# rc28c64rom.net
KiCad netlist of a schematic drawn in EAGLE
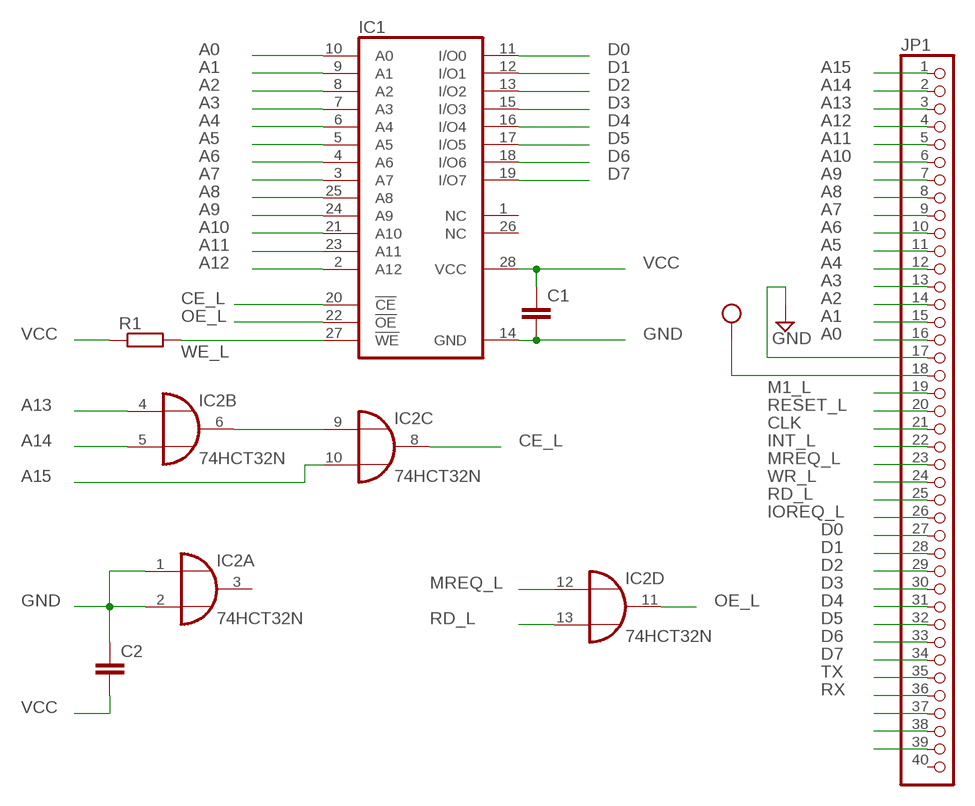
[diagram p0: schematic, sheet 1]

(export (version "E")
  (design (tool "Eeschema 10.0.6"))
  (components
    (comp (ref "C1")
      (value "C-EU025-025X050")
      (footprint "eagle-import:C025-025X050")
      (libsource (lib "eagle-import") (part "C-EU025-025X050"))
    )
    (comp (ref "C2")
      (value "C-EU025-025X050")
      (footprint "eagle-import:C025-025X050")
      (libsource (lib "eagle-import") (part "C-EU025-025X050"))
    )
    (comp (ref "IC1")
      (value "28C64C")
      (footprint "eagle-import:DIL28-6")
      (fields (field (name "MPN") "AT28C64B-15PU"))
      (libsource (lib "eagle-import") (part "28C64C"))
    )
    (comp (ref "IC2")
      (value "74HCT32N")
      (footprint "eagle-import:DIL14")
      (libsource (lib "eagle-import") (part "7432NHCT"))
    )
    (comp (ref "JP1")
      (value "PINHD-1X40")
      (footprint "eagle-import:1X40")
      (libsource (lib "eagle-import") (part "PINHD-1X40"))
    )
    (comp (ref "R1")
      (value "R-EU_0204/7")
      (footprint "eagle-import:0204_7")
      (libsource (lib "eagle-import") (part "R-EU_0204/7"))
    )
  )
  (nets
    (net (code "1") (name "/A0") (class "Default")
      (node (ref "IC1") (pin "10") (pinfunction "A0_10") (pintype "input"))
      (node (ref "JP1") (pin "16") (pinfunction "16_16") (pintype "passive"))
    )
    (net (code "2") (name "/A1") (class "Default")
      (node (ref "IC1") (pin "9") (pinfunction "A1_9") (pintype "input"))
      (node (ref "JP1") (pin "15") (pinfunction "15_15") (pintype "passive"))
    )
    (net (code "3") (name "/A2") (class "Default")
      (node (ref "IC1") (pin "8") (pinfunction "A2_8") (pintype "input"))
      (node (ref "JP1") (pin "14") (pinfunction "14_14") (pintype "passive"))
    )
    (net (code "4") (name "/A3") (class "Default")
      (node (ref "IC1") (pin "7") (pinfunction "A3_7") (pintype "input"))
      (node (ref "JP1") (pin "13") (pinfunction "13_13") (pintype "passive"))
    )
    (net (code "5") (name "/A4") (class "Default")
      (node (ref "IC1") (pin "6") (pinfunction "A4_6") (pintype "input"))
      (node (ref "JP1") (pin "12") (pinfunction "12_12") (pintype "passive"))
    )
    (net (code "6") (name "/A5") (class "Default")
      (node (ref "IC1") (pin "5") (pinfunction "A5_5") (pintype "input"))
      (node (ref "JP1") (pin "11") (pinfunction "11_11") (pintype "passive"))
    )
    (net (code "7") (name "/A6") (class "Default")
      (node (ref "IC1") (pin "4") (pinfunction "A6_4") (pintype "input"))
      (node (ref "JP1") (pin "10") (pinfunction "10_10") (pintype "passive"))
    )
    (net (code "8") (name "/A7") (class "Default")
      (node (ref "IC1") (pin "3") (pinfunction "A7_3") (pintype "input"))
      (node (ref "JP1") (pin "9") (pinfunction "9_9") (pintype "passive"))
    )
    (net (code "9") (name "/A8") (class "Default")
      (node (ref "IC1") (pin "25") (pinfunction "A8_25") (pintype "input"))
      (node (ref "JP1") (pin "8") (pinfunction "8_8") (pintype "passive"))
    )
    (net (code "10") (name "/A9") (class "Default")
      (node (ref "IC1") (pin "24") (pinfunction "A9_24") (pintype "input"))
      (node (ref "JP1") (pin "7") (pinfunction "7_7") (pintype "passive"))
    )
    (net (code "11") (name "/A10") (class "Default")
      (node (ref "IC1") (pin "21") (pinfunction "A10_21") (pintype "input"))
      (node (ref "JP1") (pin "6") (pinfunction "6_6") (pintype "passive"))
    )
    (net (code "12") (name "/A11") (class "Default")
      (node (ref "IC1") (pin "23") (pinfunction "A11_23") (pintype "input"))
      (node (ref "JP1") (pin "5") (pinfunction "5_5") (pintype "passive"))
    )
    (net (code "13") (name "/A12") (class "Default")
      (node (ref "IC1") (pin "2") (pinfunction "A12_2") (pintype "input"))
      (node (ref "JP1") (pin "4") (pinfunction "4_4") (pintype "passive"))
    )
    (net (code "14") (name "/A13") (class "Default")
      (node (ref "IC2") (pin "4") (pinfunction "I0_4") (pintype "input"))
      (node (ref "JP1") (pin "3") (pinfunction "3_3") (pintype "passive"))
    )
    (net (code "15") (name "/A14") (class "Default")
      (node (ref "IC2") (pin "5") (pinfunction "I1_5") (pintype "input"))
      (node (ref "JP1") (pin "2") (pinfunction "2_2") (pintype "passive"))
    )
    (net (code "16") (name "/A15") (class "Default")
      (node (ref "IC2") (pin "10") (pinfunction "I1_10") (pintype "input"))
      (node (ref "JP1") (pin "1") (pinfunction "1_1") (pintype "passive"))
    )
    (net (code "17") (name "/CE_L") (class "Default")
      (node (ref "IC1") (pin "20") (pinfunction "~{CE}_20") (pintype "input"))
      (node (ref "IC2") (pin "8") (pinfunction "O_8") (pintype "output"))
    )
    (net (code "18") (name "/CLK") (class "Default")
      (node (ref "JP1") (pin "21") (pinfunction "21_21") (pintype "passive"))
    )
    (net (code "19") (name "/D0") (class "Default")
      (node (ref "IC1") (pin "11") (pinfunction "I/O0_11") (pintype "bidirectional"))
      (node (ref "JP1") (pin "27") (pinfunction "27_27") (pintype "passive"))
    )
    (net (code "20") (name "/D1") (class "Default")
      (node (ref "IC1") (pin "12") (pinfunction "I/O1_12") (pintype "bidirectional"))
      (node (ref "JP1") (pin "28") (pinfunction "28_28") (pintype "passive"))
    )
    (net (code "21") (name "/D2") (class "Default")
      (node (ref "IC1") (pin "13") (pinfunction "I/O2_13") (pintype "bidirectional"))
      (node (ref "JP1") (pin "29") (pinfunction "29_29") (pintype "passive"))
    )
    (net (code "22") (name "/D3") (class "Default")
      (node (ref "IC1") (pin "15") (pinfunction "I/O3_15") (pintype "bidirectional"))
      (node (ref "JP1") (pin "30") (pinfunction "30_30") (pintype "passive"))
    )
    (net (code "23") (name "/D4") (class "Default")
      (node (ref "IC1") (pin "16") (pinfunction "I/O4_16") (pintype "bidirectional"))
      (node (ref "JP1") (pin "31") (pinfunction "31_31") (pintype "passive"))
    )
    (net (code "24") (name "/D5") (class "Default")
      (node (ref "IC1") (pin "17") (pinfunction "I/O5_17") (pintype "bidirectional"))
      (node (ref "JP1") (pin "32") (pinfunction "32_32") (pintype "passive"))
    )
    (net (code "25") (name "/D6") (class "Default")
      (node (ref "IC1") (pin "18") (pinfunction "I/O6_18") (pintype "bidirectional"))
      (node (ref "JP1") (pin "33") (pinfunction "33_33") (pintype "passive"))
    )
    (net (code "26") (name "/D7") (class "Default")
      (node (ref "IC1") (pin "19") (pinfunction "I/O7_19") (pintype "bidirectional"))
      (node (ref "JP1") (pin "34") (pinfunction "34_34") (pintype "passive"))
    )
    (net (code "27") (name "/INT_L") (class "Default")
      (node (ref "JP1") (pin "22") (pinfunction "22_22") (pintype "passive"))
    )
    (net (code "28") (name "/IOREQ_L") (class "Default")
      (node (ref "JP1") (pin "26") (pinfunction "26_26") (pintype "passive"))
    )
    (net (code "29") (name "/M1_L") (class "Default")
      (node (ref "JP1") (pin "19") (pinfunction "19_19") (pintype "passive"))
    )
    (net (code "30") (name "/MREQ_L") (class "Default")
      (node (ref "IC2") (pin "12") (pinfunction "I0_12") (pintype "input"))
      (node (ref "JP1") (pin "23") (pinfunction "23_23") (pintype "passive"))
    )
    (net (code "31") (name "/OE_L") (class "Default")
      (node (ref "IC1") (pin "22") (pinfunction "~{OE}_22") (pintype "input"))
      (node (ref "IC2") (pin "11") (pinfunction "O_11") (pintype "output"))
    )
    (net (code "32") (name "/RD_L") (class "Default")
      (node (ref "IC2") (pin "13") (pinfunction "I1_13") (pintype "input"))
      (node (ref "JP1") (pin "25") (pinfunction "25_25") (pintype "passive"))
    )
    (net (code "33") (name "/RESET_L") (class "Default")
      (node (ref "JP1") (pin "20") (pinfunction "20_20") (pintype "passive"))
    )
    (net (code "34") (name "/RX") (class "Default")
      (node (ref "JP1") (pin "36") (pinfunction "36_36") (pintype "passive"))
    )
    (net (code "35") (name "/TX") (class "Default")
      (node (ref "JP1") (pin "35") (pinfunction "35_35") (pintype "passive"))
    )
    (net (code "36") (name "/WE_L") (class "Default")
      (node (ref "IC1") (pin "27") (pinfunction "~{WE}_27") (pintype "input"))
      (node (ref "R1") (pin "2") (pinfunction "2_2") (pintype "passive"))
    )
    (net (code "37") (name "/WR_L") (class "Default")
      (node (ref "JP1") (pin "24") (pinfunction "24_24") (pintype "passive"))
    )
    (net (code "38") (name "GND") (class "Default")
      (node (ref "C1") (pin "2") (pinfunction "2_2") (pintype "passive"))
      (node (ref "C2") (pin "1") (pinfunction "1_1") (pintype "passive"))
      (node (ref "IC1") (pin "14") (pinfunction "GND_14") (pintype "power_in"))
      (node (ref "IC2") (pin "1") (pinfunction "I0_1") (pintype "input"))
      (node (ref "IC2") (pin "2") (pinfunction "I1_2") (pintype "input"))
      (node (ref "JP1") (pin "17") (pinfunction "17_17") (pintype "passive"))
    )
    (net (code "39") (name "Net-(IC2B-O)") (class "Default")
      (node (ref "IC2") (pin "6") (pinfunction "O_6") (pintype "output"))
      (node (ref "IC2") (pin "9") (pinfunction "I0_9") (pintype "input"))
    )
    (net (code "40") (name "VCC") (class "Default")
      (node (ref "C1") (pin "1") (pinfunction "1_1") (pintype "passive"))
      (node (ref "C2") (pin "2") (pinfunction "2_2") (pintype "passive"))
      (node (ref "IC1") (pin "28") (pinfunction "VCC_28") (pintype "power_in"))
      (node (ref "JP1") (pin "18") (pinfunction "18_18") (pintype "passive"))
      (node (ref "R1") (pin "1") (pinfunction "1_1") (pintype "passive"))
    )
    (net (code "41") (name "unconnected-(IC1-NC-Pad1)") (class "Default")
      (node (ref "IC1") (pin "1") (pinfunction "NC_1") (pintype "no_connect"))
    )
    (net (code "42") (name "unconnected-(IC1-NC-Pad26)") (class "Default")
      (node (ref "IC1") (pin "26") (pinfunction "NC_26") (pintype "no_connect"))
    )
    (net (code "43") (name "unconnected-(IC2A-O-Pad3)") (class "Default")
      (node (ref "IC2") (pin "3") (pinfunction "O_3") (pintype "output"))
    )
    (net (code "44") (name "unconnected-(JP1-Pad37)") (class "Default")
      (node (ref "JP1") (pin "37") (pinfunction "37_37") (pintype "passive"))
    )
    (net (code "45") (name "unconnected-(JP1-Pad38)") (class "Default")
      (node (ref "JP1") (pin "38") (pinfunction "38_38") (pintype "passive"))
    )
    (net (code "46") (name "unconnected-(JP1-Pad39)") (class "Default")
      (node (ref "JP1") (pin "39") (pinfunction "39_39") (pintype "passive"))
    )
    (net (code "47") (name "unconnected-(JP1-Pad40)") (class "Default")
      (node (ref "JP1") (pin "40") (pinfunction "40_40") (pintype "passive"))
    )
  )
)
